# as14120_fpga_ttl.net
KiCad netlist of a schematic drawn in Altium Designer
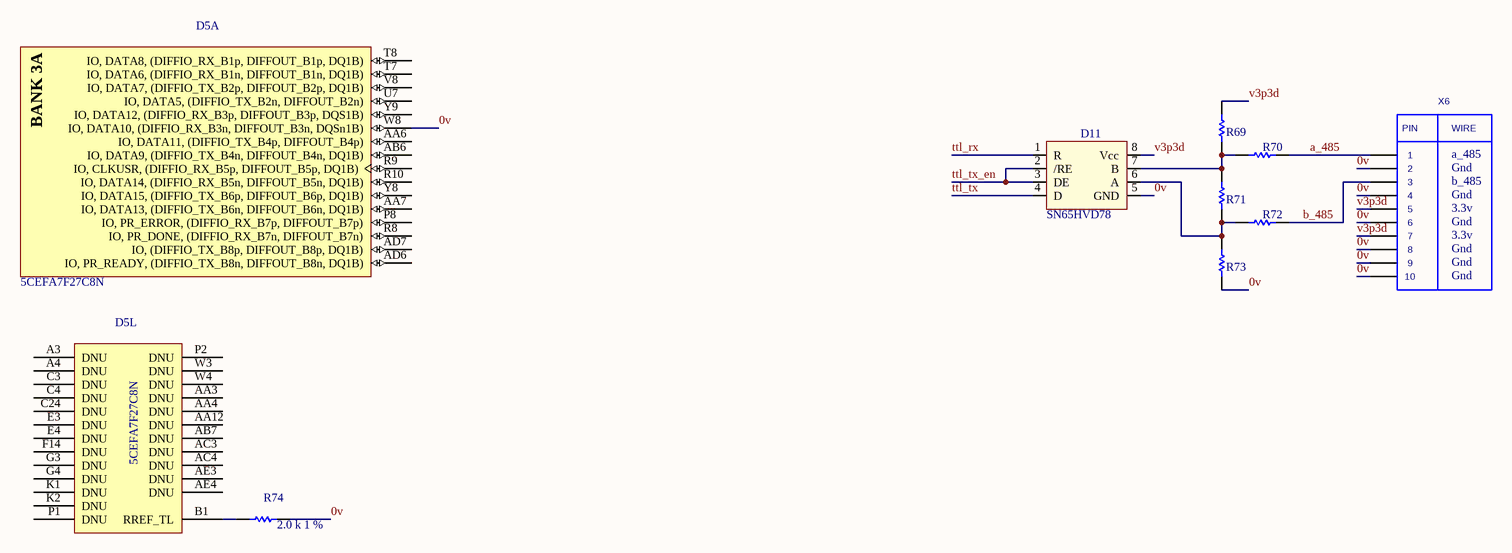
[diagram p0: as14120_fpga_ttl.SchDoc]

(export (version "E")
  (design (tool "Eeschema 10.0.6"))
  (components
    (comp (ref "D5")
      (value "5CEFA7F27C8N")
      (footprint "ALTR-672-FBGA-2000A")
      (fields (field (name "MANUFACTURER") "Altera"))
      (libsource (lib "Altera Cyclone V E") (part "5CEFA7F27C8N"))
    )
    (comp (ref "D11") (value "SN65HVD78") (footprint "8S1_M") (libsource (lib "as14120") (part "SN65HVD78")))
    (comp (ref "R69")
      (value "1K 1% 0805(2012)")
      (footprint "RESC0805(2012)_L")
      (description "1K 0.125W 1% 0805 (2012 Metric)  SMD")
      (fields (field (name "TOLERANCE") "1 %") (field (name "POWER") "0.125 W"))
      (libsource (lib "as14120") (part "RES_0805"))
    )
    (comp (ref "R70")
      (value "1K 1% 0805(2012)")
      (footprint "RESC0805(2012)_L")
      (description "1K 0.125W 1% 0805 (2012 Metric)  SMD")
      (fields (field (name "TOLERANCE") "1 %") (field (name "POWER") "0.125 W"))
      (libsource (lib "as14120") (part "RES_0805"))
    )
    (comp (ref "R71")
      (value "1K 1% 0805(2012)")
      (footprint "RESC0805(2012)_L")
      (description "1K 0.125W 1% 0805 (2012 Metric)  SMD")
      (fields (field (name "TOLERANCE") "1 %") (field (name "POWER") "0.125 W"))
      (libsource (lib "as14120") (part "RES_0805"))
    )
    (comp (ref "R72")
      (value "1K 1% 0805(2012)")
      (footprint "RESC0805(2012)_L")
      (description "1K 0.125W 1% 0805 (2012 Metric)  SMD")
      (fields (field (name "TOLERANCE") "1 %") (field (name "POWER") "0.125 W"))
      (libsource (lib "as14120") (part "RES_0805"))
    )
    (comp (ref "R73")
      (value "1K 1% 0805(2012)")
      (footprint "RESC0805(2012)_L")
      (description "1K 0.125W 1% 0805 (2012 Metric)  SMD")
      (fields (field (name "TOLERANCE") "1 %") (field (name "POWER") "0.125 W"))
      (libsource (lib "as14120") (part "RES_0805"))
    )
    (comp (ref "R74")
      (value "2.0 k")
      (footprint "RESC0805(2012)_L")
      (description "1K 0.125W 1% 0805 (2012 Metric)  SMD")
      (fields
        (field (name "TOLERANCE") "1 %")
        (field (name "POWER") "0.125 W")
        (field (name "Comment") "1K 1% 0805(2012)")
      )
      (libsource (lib "as14120") (part "RES_0805"))
    )
    (comp (ref "X6") (value "IDC10") (footprint "IDC10M") (libsource (lib "alexsb") (part "IDC10")))
  )
  (nets
    (net (code "1") (name "/0v") (class "Default")
      (node (ref "D11") (pin "5") (pinfunction "GND_5") (pintype "passive"))
      (node (ref "D5") (pin "W8") (pinfunction "IO,_DATA10,_(DIFFIO_RX_B3n,_DIFFOUT_B3n,_DQSn1B)_W8") (pintype "bidirectional"))
      (node (ref "R73") (pin "1") (pinfunction "1_1") (pintype "passive"))
      (node (ref "R74") (pin "2") (pinfunction "2_2") (pintype "passive"))
      (node (ref "X6") (pin "10") (pintype "passive"))
      (node (ref "X6") (pin "2") (pintype "passive"))
      (node (ref "X6") (pin "4") (pintype "passive"))
      (node (ref "X6") (pin "6") (pintype "passive"))
      (node (ref "X6") (pin "8") (pintype "passive"))
      (node (ref "X6") (pin "9") (pintype "passive"))
    )
    (net (code "2") (name "/a_485") (class "Default")
      (node (ref "R70") (pin "2") (pinfunction "2_2") (pintype "passive"))
      (node (ref "X6") (pin "1") (pintype "passive"))
    )
    (net (code "3") (name "/b_485") (class "Default")
      (node (ref "R72") (pin "2") (pinfunction "2_2") (pintype "passive"))
      (node (ref "X6") (pin "3") (pintype "passive"))
    )
    (net (code "4") (name "/ttl_rx") (class "Default")
      (node (ref "D11") (pin "1") (pinfunction "R_1") (pintype "passive"))
    )
    (net (code "5") (name "/ttl_tx") (class "Default")
      (node (ref "D11") (pin "4") (pinfunction "D_4") (pintype "passive"))
    )
    (net (code "6") (name "/ttl_tx_en") (class "Default")
      (node (ref "D11") (pin "2") (pinfunction "/RE_2") (pintype "passive"))
      (node (ref "D11") (pin "3") (pinfunction "DE_3") (pintype "passive"))
    )
    (net (code "7") (name "/v3p3d") (class "Default")
      (node (ref "D11") (pin "8") (pinfunction "Vcc_8") (pintype "passive"))
      (node (ref "R69") (pin "2") (pinfunction "2_2") (pintype "passive"))
      (node (ref "X6") (pin "5") (pintype "passive"))
      (node (ref "X6") (pin "7") (pintype "passive"))
    )
    (net (code "8") (name "Net-(D5L-RREF_TL)") (class "Default")
      (node (ref "D5") (pin "B1") (pinfunction "RREF_TL_B1") (pintype "passive"))
      (node (ref "R74") (pin "1") (pinfunction "1_1") (pintype "passive"))
    )
    (net (code "9") (name "Net-(D11-A)") (class "Default")
      (node (ref "D11") (pin "6") (pinfunction "A_6") (pintype "passive"))
      (node (ref "R71") (pin "1") (pinfunction "1_1") (pintype "passive"))
      (node (ref "R72") (pin "1") (pinfunction "1_1") (pintype "passive"))
      (node (ref "R73") (pin "2") (pinfunction "2_2") (pintype "passive"))
    )
    (net (code "10") (name "Net-(D11-B)") (class "Default")
      (node (ref "D11") (pin "7") (pinfunction "B_7") (pintype "passive"))
      (node (ref "R69") (pin "1") (pinfunction "1_1") (pintype "passive"))
      (node (ref "R70") (pin "1") (pinfunction "1_1") (pintype "passive"))
      (node (ref "R71") (pin "2") (pinfunction "2_2") (pintype "passive"))
    )
    (net (code "11") (name "unconnected-(D5A-IO,_(DIFFIO_TX_B8p,_DIFFOUT_B8p,_DQ1B)-PadAD7)") (class "Default")
      (node (ref "D5") (pin "AD7") (pinfunction "IO,_(DIFFIO_TX_B8p,_DIFFOUT_B8p,_DQ1B)_AD7") (pintype "bidirectional"))
    )
    (net (code "12") (name "unconnected-(D5A-IO,_CLKUSR,_(DIFFIO_RX_B5p,_DIFFOUT_B5p,_DQ1B)-PadR9)") (class "Default")
      (node (ref "D5") (pin "R9") (pinfunction "IO,_CLKUSR,_(DIFFIO_RX_B5p,_DIFFOUT_B5p,_DQ1B)_R9") (pintype "bidirectional"))
    )
    (net (code "13") (name "unconnected-(D5A-IO,_DATA5,_(DIFFIO_TX_B2n,_DIFFOUT_B2n)-PadU7)") (class "Default")
      (node (ref "D5") (pin "U7") (pinfunction "IO,_DATA5,_(DIFFIO_TX_B2n,_DIFFOUT_B2n)_U7") (pintype "bidirectional"))
    )
    (net (code "14") (name "unconnected-(D5A-IO,_DATA6,_(DIFFIO_RX_B1n,_DIFFOUT_B1n,_DQ1B)-PadT7)") (class "Default")
      (node (ref "D5") (pin "T7") (pinfunction "IO,_DATA6,_(DIFFIO_RX_B1n,_DIFFOUT_B1n,_DQ1B)_T7") (pintype "bidirectional"))
    )
    (net (code "15") (name "unconnected-(D5A-IO,_DATA7,_(DIFFIO_TX_B2p,_DIFFOUT_B2p,_DQ1B)-PadV8)") (class "Default")
      (node (ref "D5") (pin "V8") (pinfunction "IO,_DATA7,_(DIFFIO_TX_B2p,_DIFFOUT_B2p,_DQ1B)_V8") (pintype "bidirectional"))
    )
    (net (code "16") (name "unconnected-(D5A-IO,_DATA8,_(DIFFIO_RX_B1p,_DIFFOUT_B1p,_DQ1B)-PadT8)") (class "Default")
      (node (ref "D5") (pin "T8") (pinfunction "IO,_DATA8,_(DIFFIO_RX_B1p,_DIFFOUT_B1p,_DQ1B)_T8") (pintype "bidirectional"))
    )
    (net (code "17") (name "unconnected-(D5A-IO,_DATA9,_(DIFFIO_TX_B4n,_DIFFOUT_B4n,_DQ1B)-PadAB6)") (class "Default")
      (node (ref "D5") (pin "AB6") (pinfunction "IO,_DATA9,_(DIFFIO_TX_B4n,_DIFFOUT_B4n,_DQ1B)_AB6") (pintype "bidirectional"))
    )
    (net (code "18") (name "unconnected-(D5A-IO,_DATA11,_(DIFFIO_TX_B4p,_DIFFOUT_B4p)-PadAA6)") (class "Default")
      (node (ref "D5") (pin "AA6") (pinfunction "IO,_DATA11,_(DIFFIO_TX_B4p,_DIFFOUT_B4p)_AA6") (pintype "bidirectional"))
    )
    (net (code "19") (name "unconnected-(D5A-IO,_DATA12,_(DIFFIO_RX_B3p,_DIFFOUT_B3p,_DQS1B)-PadY9)") (class "Default")
      (node (ref "D5") (pin "Y9") (pinfunction "IO,_DATA12,_(DIFFIO_RX_B3p,_DIFFOUT_B3p,_DQS1B)_Y9") (pintype "bidirectional"))
    )
    (net (code "20") (name "unconnected-(D5A-IO,_DATA13,_(DIFFIO_TX_B6n,_DIFFOUT_B6n,_DQ1B)-PadAA7)") (class "Default")
      (node (ref "D5") (pin "AA7") (pinfunction "IO,_DATA13,_(DIFFIO_TX_B6n,_DIFFOUT_B6n,_DQ1B)_AA7") (pintype "bidirectional"))
    )
    (net (code "21") (name "unconnected-(D5A-IO,_DATA14,_(DIFFIO_RX_B5n,_DIFFOUT_B5n,_DQ1B)-PadR10)") (class "Default")
      (node (ref "D5") (pin "R10") (pinfunction "IO,_DATA14,_(DIFFIO_RX_B5n,_DIFFOUT_B5n,_DQ1B)_R10") (pintype "bidirectional"))
    )
    (net (code "22") (name "unconnected-(D5A-IO,_DATA15,_(DIFFIO_TX_B6p,_DIFFOUT_B6p,_DQ1B)-PadY8)") (class "Default")
      (node (ref "D5") (pin "Y8") (pinfunction "IO,_DATA15,_(DIFFIO_TX_B6p,_DIFFOUT_B6p,_DQ1B)_Y8") (pintype "bidirectional"))
    )
    (net (code "23") (name "unconnected-(D5A-IO,_PR_DONE,_(DIFFIO_RX_B7n,_DIFFOUT_B7n)-PadR8)") (class "Default")
      (node (ref "D5") (pin "R8") (pinfunction "IO,_PR_DONE,_(DIFFIO_RX_B7n,_DIFFOUT_B7n)_R8") (pintype "bidirectional"))
    )
    (net (code "24") (name "unconnected-(D5A-IO,_PR_ERROR,_(DIFFIO_RX_B7p,_DIFFOUT_B7p)-PadP8)") (class "Default")
      (node (ref "D5") (pin "P8") (pinfunction "IO,_PR_ERROR,_(DIFFIO_RX_B7p,_DIFFOUT_B7p)_P8") (pintype "bidirectional"))
    )
    (net (code "25") (name "unconnected-(D5A-IO,_PR_READY,_(DIFFIO_TX_B8n,_DIFFOUT_B8n,_DQ1B)-PadAD6)") (class "Default")
      (node (ref "D5") (pin "AD6") (pinfunction "IO,_PR_READY,_(DIFFIO_TX_B8n,_DIFFOUT_B8n,_DQ1B)_AD6") (pintype "bidirectional"))
    )
    (net (code "26") (name "unconnected-(D5L-DNU-PadA3)") (class "Default")
      (node (ref "D5") (pin "A3") (pinfunction "DNU_A3") (pintype "passive"))
    )
    (net (code "27") (name "unconnected-(D5L-DNU-PadA4)") (class "Default")
      (node (ref "D5") (pin "A4") (pinfunction "DNU_A4") (pintype "passive"))
    )
    (net (code "28") (name "unconnected-(D5L-DNU-PadAA3)") (class "Default")
      (node (ref "D5") (pin "AA3") (pinfunction "DNU_AA3") (pintype "passive"))
    )
    (net (code "29") (name "unconnected-(D5L-DNU-PadAA4)") (class "Default")
      (node (ref "D5") (pin "AA4") (pinfunction "DNU_AA4") (pintype "passive"))
    )
    (net (code "30") (name "unconnected-(D5L-DNU-PadAA12)") (class "Default")
      (node (ref "D5") (pin "AA12") (pinfunction "DNU_AA12") (pintype "passive"))
    )
    (net (code "31") (name "unconnected-(D5L-DNU-PadAB7)") (class "Default")
      (node (ref "D5") (pin "AB7") (pinfunction "DNU_AB7") (pintype "passive"))
    )
    (net (code "32") (name "unconnected-(D5L-DNU-PadAC3)") (class "Default")
      (node (ref "D5") (pin "AC3") (pinfunction "DNU_AC3") (pintype "passive"))
    )
    (net (code "33") (name "unconnected-(D5L-DNU-PadAC4)") (class "Default")
      (node (ref "D5") (pin "AC4") (pinfunction "DNU_AC4") (pintype "passive"))
    )
    (net (code "34") (name "unconnected-(D5L-DNU-PadAE3)") (class "Default")
      (node (ref "D5") (pin "AE3") (pinfunction "DNU_AE3") (pintype "passive"))
    )
    (net (code "35") (name "unconnected-(D5L-DNU-PadAE4)") (class "Default")
      (node (ref "D5") (pin "AE4") (pinfunction "DNU_AE4") (pintype "passive"))
    )
    (net (code "36") (name "unconnected-(D5L-DNU-PadC3)") (class "Default")
      (node (ref "D5") (pin "C3") (pinfunction "DNU_C3") (pintype "passive"))
    )
    (net (code "37") (name "unconnected-(D5L-DNU-PadC4)") (class "Default")
      (node (ref "D5") (pin "C4") (pinfunction "DNU_C4") (pintype "passive"))
    )
    (net (code "38") (name "unconnected-(D5L-DNU-PadC24)") (class "Default")
      (node (ref "D5") (pin "C24") (pinfunction "DNU_C24") (pintype "passive"))
    )
    (net (code "39") (name "unconnected-(D5L-DNU-PadE3)") (class "Default")
      (node (ref "D5") (pin "E3") (pinfunction "DNU_E3") (pintype "passive"))
    )
    (net (code "40") (name "unconnected-(D5L-DNU-PadE4)") (class "Default")
      (node (ref "D5") (pin "E4") (pinfunction "DNU_E4") (pintype "passive"))
    )
    (net (code "41") (name "unconnected-(D5L-DNU-PadF14)") (class "Default")
      (node (ref "D5") (pin "F14") (pinfunction "DNU_F14") (pintype "passive"))
    )
    (net (code "42") (name "unconnected-(D5L-DNU-PadG3)") (class "Default")
      (node (ref "D5") (pin "G3") (pinfunction "DNU_G3") (pintype "passive"))
    )
    (net (code "43") (name "unconnected-(D5L-DNU-PadG4)") (class "Default")
      (node (ref "D5") (pin "G4") (pinfunction "DNU_G4") (pintype "passive"))
    )
    (net (code "44") (name "unconnected-(D5L-DNU-PadK1)") (class "Default")
      (node (ref "D5") (pin "K1") (pinfunction "DNU_K1") (pintype "passive"))
    )
    (net (code "45") (name "unconnected-(D5L-DNU-PadK2)") (class "Default")
      (node (ref "D5") (pin "K2") (pinfunction "DNU_K2") (pintype "passive"))
    )
    (net (code "46") (name "unconnected-(D5L-DNU-PadP1)") (class "Default")
      (node (ref "D5") (pin "P1") (pinfunction "DNU_P1") (pintype "passive"))
    )
    (net (code "47") (name "unconnected-(D5L-DNU-PadP2)") (class "Default")
      (node (ref "D5") (pin "P2") (pinfunction "DNU_P2") (pintype "passive"))
    )
    (net (code "48") (name "unconnected-(D5L-DNU-PadW3)") (class "Default")
      (node (ref "D5") (pin "W3") (pinfunction "DNU_W3") (pintype "passive"))
    )
    (net (code "49") (name "unconnected-(D5L-DNU-PadW4)") (class "Default")
      (node (ref "D5") (pin "W4") (pinfunction "DNU_W4") (pintype "passive"))
    )
  )
)
